# fitness_logger.net
KiCad netlist of a schematic drawn in EAGLE
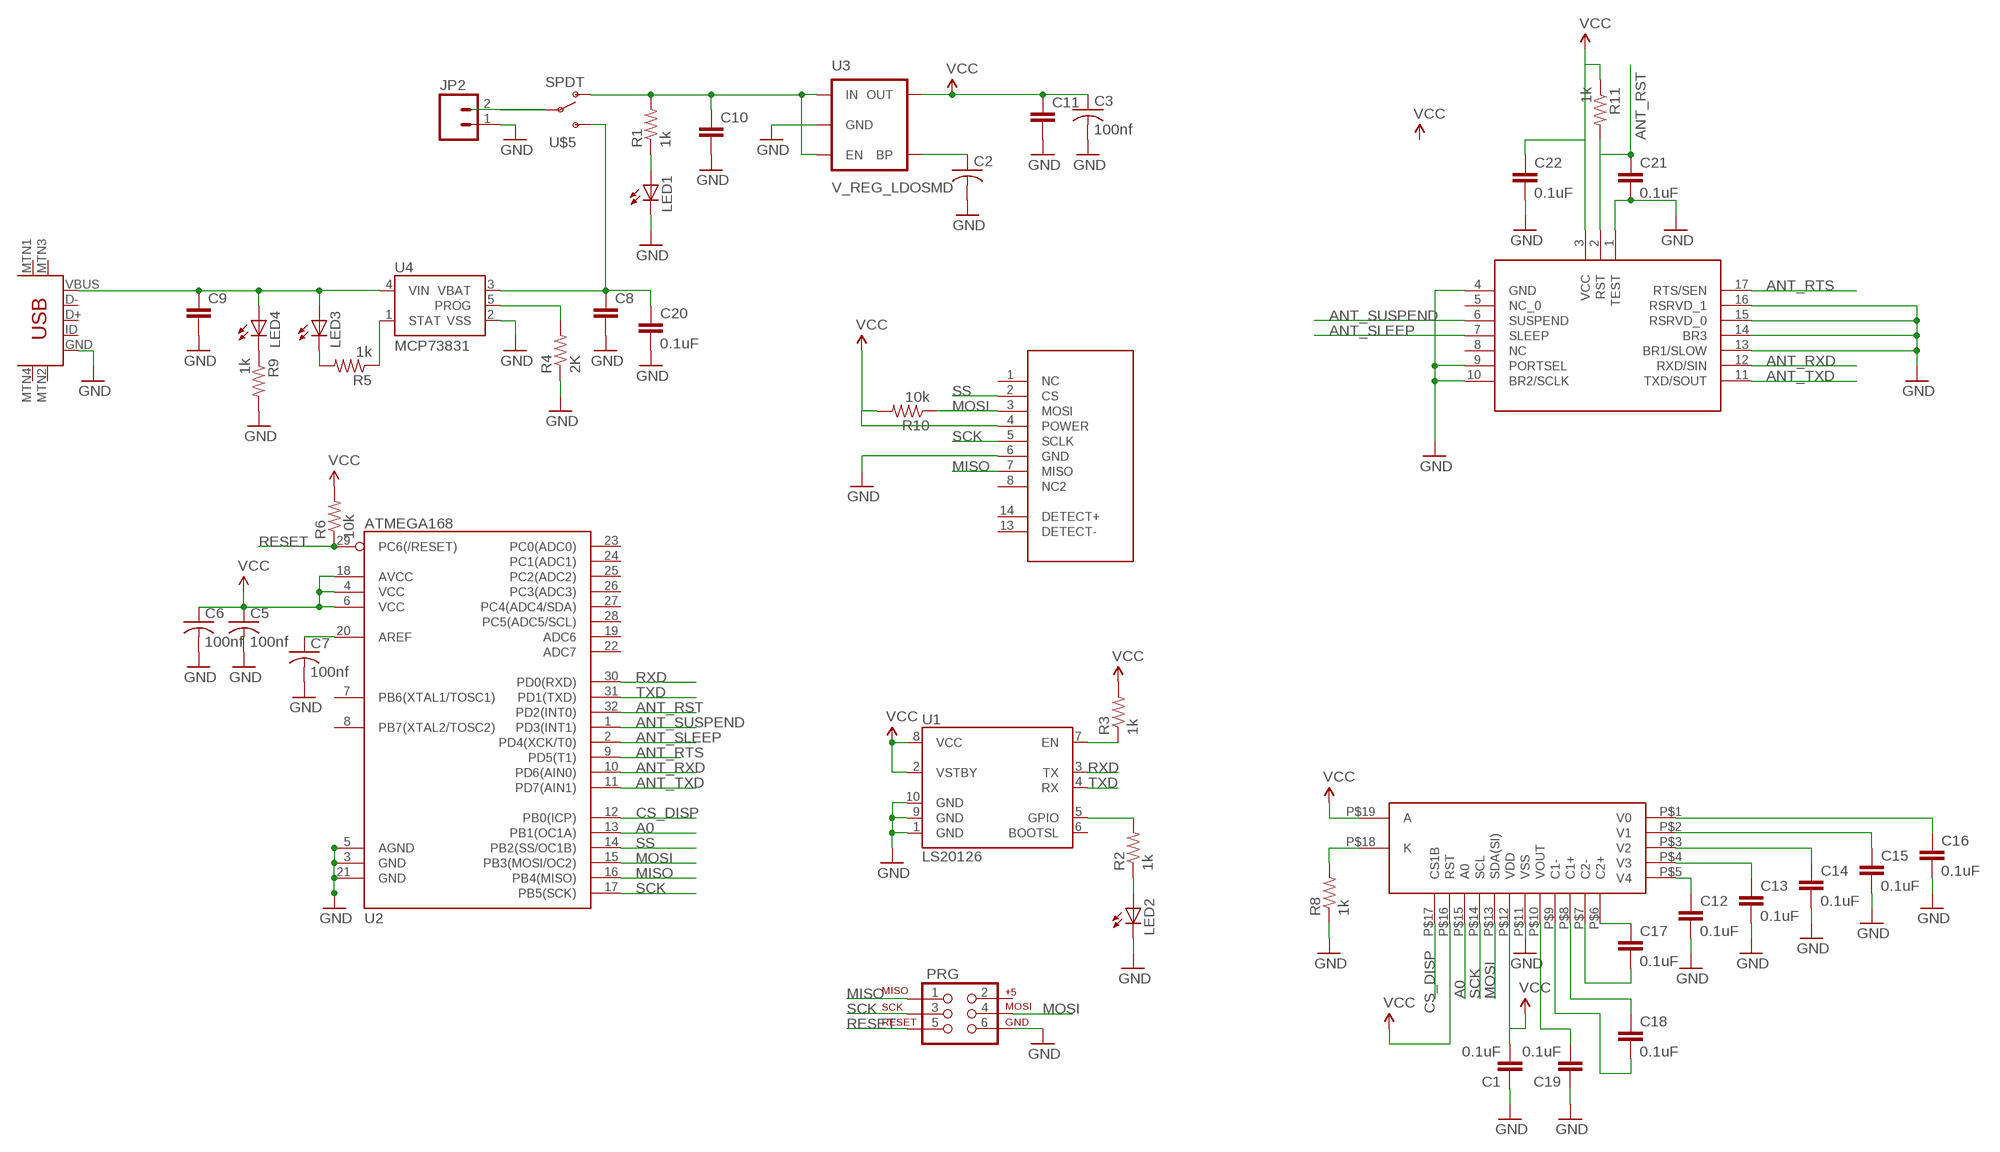
[diagram p0: schematic, sheet 1]

(export (version "E")
  (design (tool "Eeschema 10.0.6"))
  (components
    (comp (ref "C1")
      (value "0.1uF")
      (footprint "eagle-import:0402-CAP")
      (libsource (lib "eagle-import") (part "0.1UF-25V(+80/-20%)(0603)"))
    )
    (comp (ref "C2")
      (value "C-USC0603")
      (footprint "eagle-import:C0603")
      (libsource (lib "eagle-import") (part "C-USC0603"))
    )
    (comp (ref "C3")
      (value "100nf")
      (footprint "eagle-import:C0603")
      (libsource (lib "eagle-import") (part "C-USC0603"))
    )
    (comp (ref "C5")
      (value "100nf")
      (footprint "eagle-import:C0603")
      (libsource (lib "eagle-import") (part "C-USC0603"))
    )
    (comp (ref "C6")
      (value "100nf")
      (footprint "eagle-import:C0603")
      (libsource (lib "eagle-import") (part "C-USC0603"))
    )
    (comp (ref "C7")
      (value "100nf")
      (footprint "eagle-import:C0603")
      (libsource (lib "eagle-import") (part "C-USC0603"))
    )
    (comp (ref "C8")
      (value "CAP1210")
      (footprint "eagle-import:1210")
      (libsource (lib "eagle-import") (part "CAP1210"))
    )
    (comp (ref "C9")
      (value "CAP1210")
      (footprint "eagle-import:1210")
      (libsource (lib "eagle-import") (part "CAP1210"))
    )
    (comp (ref "C10")
      (value "CAP1210")
      (footprint "eagle-import:1210")
      (libsource (lib "eagle-import") (part "CAP1210"))
    )
    (comp (ref "C11")
      (value "CAP1210")
      (footprint "eagle-import:1210")
      (libsource (lib "eagle-import") (part "CAP1210"))
    )
    (comp (ref "C12")
      (value "0.1uF")
      (footprint "eagle-import:0402-CAP")
      (libsource (lib "eagle-import") (part "0.1UF-25V(+80/-20%)(0603)"))
    )
    (comp (ref "C13")
      (value "0.1uF")
      (footprint "eagle-import:0402-CAP")
      (libsource (lib "eagle-import") (part "0.1UF-25V(+80/-20%)(0603)"))
    )
    (comp (ref "C14")
      (value "0.1uF")
      (footprint "eagle-import:0402-CAP")
      (libsource (lib "eagle-import") (part "0.1UF-25V(+80/-20%)(0603)"))
    )
    (comp (ref "C15")
      (value "0.1uF")
      (footprint "eagle-import:0402-CAP")
      (libsource (lib "eagle-import") (part "0.1UF-25V(+80/-20%)(0603)"))
    )
    (comp (ref "C16")
      (value "0.1uF")
      (footprint "eagle-import:0402-CAP")
      (libsource (lib "eagle-import") (part "0.1UF-25V(+80/-20%)(0603)"))
    )
    (comp (ref "C17")
      (value "0.1uF")
      (footprint "eagle-import:0402-CAP")
      (libsource (lib "eagle-import") (part "0.1UF-25V(+80/-20%)(0603)"))
    )
    (comp (ref "C18")
      (value "0.1uF")
      (footprint "eagle-import:0402-CAP")
      (libsource (lib "eagle-import") (part "0.1UF-25V(+80/-20%)(0603)"))
    )
    (comp (ref "C19")
      (value "0.1uF")
      (footprint "eagle-import:0402-CAP")
      (libsource (lib "eagle-import") (part "0.1UF-25V(+80/-20%)(0603)"))
    )
    (comp (ref "C20")
      (value "0.1uF")
      (footprint "eagle-import:0402-CAP")
      (libsource (lib "eagle-import") (part "0.1UF-25V(+80/-20%)(0603)"))
    )
    (comp (ref "C21")
      (value "0.1uF")
      (footprint "eagle-import:0402-CAP")
      (libsource (lib "eagle-import") (part "0.1UF-25V(+80/-20%)(0603)"))
    )
    (comp (ref "C22")
      (value "0.1uF")
      (footprint "eagle-import:0402-CAP")
      (libsource (lib "eagle-import") (part "0.1UF-25V(+80/-20%)(0603)"))
    )
    (comp (ref "JP2")
      (value "M02PTH3")
      (footprint "eagle-import:1X02_LONGPADS")
      (libsource (lib "eagle-import") (part "M02PTH3"))
    )
    (comp (ref "LED1")
      (value "LEDCHIPLED_0603")
      (footprint "eagle-import:CHIPLED_0603")
      (libsource (lib "eagle-import") (part "LEDCHIPLED_0603"))
    )
    (comp (ref "LED2")
      (value "LEDCHIPLED_0603")
      (footprint "eagle-import:CHIPLED_0603")
      (libsource (lib "eagle-import") (part "LEDCHIPLED_0603"))
    )
    (comp (ref "LED3")
      (value "LEDCHIPLED_0603")
      (footprint "eagle-import:CHIPLED_0603")
      (libsource (lib "eagle-import") (part "LEDCHIPLED_0603"))
    )
    (comp (ref "LED4")
      (value "LEDCHIPLED_0603")
      (footprint "eagle-import:CHIPLED_0603")
      (libsource (lib "eagle-import") (part "LEDCHIPLED_0603"))
    )
    (comp (ref "PRG")
      (value "AVR_SPI_PRG_6PTH")
      (footprint "eagle-import:2X3")
      (libsource (lib "eagle-import") (part "AVR_SPI_PRG_6PTH"))
    )
    (comp (ref "R1")
      (value "1k")
      (footprint "eagle-import:0603-RES")
      (libsource (lib "eagle-import") (part "RESISTOR0603-RES"))
    )
    (comp (ref "R2")
      (value "1k")
      (footprint "eagle-import:0603-RES")
      (libsource (lib "eagle-import") (part "RESISTOR0603-RES"))
    )
    (comp (ref "R3")
      (value "1k")
      (footprint "eagle-import:0603-RES")
      (libsource (lib "eagle-import") (part "RESISTOR0603-RES"))
    )
    (comp (ref "R4")
      (value "2K")
      (footprint "eagle-import:0603-RES")
      (libsource (lib "eagle-import") (part "RESISTOR0603-RES"))
    )
    (comp (ref "R5")
      (value "1k")
      (footprint "eagle-import:0603-RES")
      (libsource (lib "eagle-import") (part "RESISTOR0603-RES"))
    )
    (comp (ref "R6")
      (value "10k")
      (footprint "eagle-import:0603-RES")
      (libsource (lib "eagle-import") (part "RESISTOR0603-RES"))
    )
    (comp (ref "R8")
      (value "1k")
      (footprint "eagle-import:0603-RES")
      (libsource (lib "eagle-import") (part "RESISTOR0603-RES"))
    )
    (comp (ref "R9")
      (value "1k")
      (footprint "eagle-import:0603-RES")
      (libsource (lib "eagle-import") (part "RESISTOR0603-RES"))
    )
    (comp (ref "R10")
      (value "10k")
      (footprint "eagle-import:0603-RES")
      (libsource (lib "eagle-import") (part "RESISTOR0603-RES"))
    )
    (comp (ref "R11")
      (value "1k")
      (footprint "eagle-import:0603-RES")
      (libsource (lib "eagle-import") (part "RESISTOR0603-RES"))
    )
    (comp (ref "U$1")
      (value "USB-MINIB-5PIN")
      (footprint "eagle-import:USB-MINIB")
      (libsource (lib "eagle-import") (part "USB-MINIB-5PIN"))
    )
    (comp (ref "U$2")
      (value "ANTAP281M4IB")
      (footprint "eagle-import:ANTAP281M4IB")
      (libsource (lib "eagle-import") (part "ANTAP281M4IB"))
    )
    (comp (ref "U$3")
      (value "NHD-C12832A1Z")
      (footprint "eagle-import:NHD-C12832A1Z")
      (libsource (lib "eagle-import") (part "NHD-C12832A1Z"))
    )
    (comp (ref "U$4")
      (value "MICRO_SD")
      (footprint "eagle-import:MICRO_SD_MOLEX")
      (libsource (lib "eagle-import") (part "MICRO_SD"))
    )
    (comp (ref "U$5")
      (value "SPDT")
      (footprint "eagle-import:SPDT-SMD")
      (libsource (lib "eagle-import") (part "SPDT"))
    )
    (comp (ref "U1")
      (value "LS20126")
      (footprint "eagle-import:LS20126")
      (libsource (lib "eagle-import") (part "LS20126"))
    )
    (comp (ref "U2")
      (value "ATMEGA168")
      (footprint "eagle-import:TQFP32-08")
      (libsource (lib "eagle-import") (part "ATMEGA168"))
    )
    (comp (ref "U3")
      (value "V_REG_LDOSMD")
      (footprint "eagle-import:SOT23-5")
      (libsource (lib "eagle-import") (part "V_REG_LDOSMD"))
    )
    (comp (ref "U4")
      (value "MCP73831")
      (footprint "eagle-import:SOT23-5")
      (libsource (lib "eagle-import") (part "MCP73831"))
    )
  )
  (nets
    (net (code "1") (name "/A0") (class "Default")
      (node (ref "U$3") (pin "P$15") (pinfunction "A0_P$15") (pintype "bidirectional"))
      (node (ref "U2") (pin "13") (pinfunction "PB1(OC1A)_13") (pintype "bidirectional"))
    )
    (net (code "2") (name "/ANT_RST") (class "Default")
      (node (ref "C21") (pin "1") (pinfunction "1_1") (pintype "passive"))
      (node (ref "R11") (pin "2") (pinfunction "2_2") (pintype "passive"))
      (node (ref "U$2") (pin "2") (pinfunction "RST_2") (pintype "bidirectional"))
      (node (ref "U2") (pin "32") (pinfunction "PD2(INT0)_32") (pintype "bidirectional"))
    )
    (net (code "3") (name "/ANT_RTS") (class "Default")
      (node (ref "U$2") (pin "17") (pinfunction "RTS/SEN_17") (pintype "bidirectional"))
      (node (ref "U2") (pin "9") (pinfunction "PD5(T1)_9") (pintype "bidirectional"))
    )
    (net (code "4") (name "/ANT_RXD") (class "Default")
      (node (ref "U$2") (pin "12") (pinfunction "RXD/SIN_12") (pintype "bidirectional"))
      (node (ref "U2") (pin "10") (pinfunction "PD6(AIN0)_10") (pintype "bidirectional"))
    )
    (net (code "5") (name "/ANT_SLEEP") (class "Default")
      (node (ref "U$2") (pin "7") (pinfunction "SLEEP_7") (pintype "bidirectional"))
      (node (ref "U2") (pin "2") (pinfunction "PD4(XCK/T0)_2") (pintype "bidirectional"))
    )
    (net (code "6") (name "/ANT_SUSPEND") (class "Default")
      (node (ref "U$2") (pin "6") (pinfunction "SUSPEND_6") (pintype "bidirectional"))
      (node (ref "U2") (pin "1") (pinfunction "PD3(INT1)_1") (pintype "bidirectional"))
    )
    (net (code "7") (name "/ANT_TXD") (class "Default")
      (node (ref "U$2") (pin "11") (pinfunction "TXD/SOUT_11") (pintype "bidirectional"))
      (node (ref "U2") (pin "11") (pinfunction "PD7(AIN1)_11") (pintype "bidirectional"))
    )
    (net (code "8") (name "/CS_DISP") (class "Default")
      (node (ref "U$3") (pin "P$17") (pinfunction "CS1B_P$17") (pintype "bidirectional"))
      (node (ref "U2") (pin "12") (pinfunction "PB0(ICP)_12") (pintype "bidirectional"))
    )
    (net (code "9") (name "/MISO") (class "Default")
      (node (ref "PRG") (pin "1") (pinfunction "1_1") (pintype "passive"))
      (node (ref "U$4") (pin "7") (pinfunction "MISO_7") (pintype "bidirectional"))
      (node (ref "U2") (pin "16") (pinfunction "PB4(MISO)_16") (pintype "bidirectional"))
    )
    (net (code "10") (name "/MOSI") (class "Default")
      (node (ref "PRG") (pin "4") (pinfunction "4_4") (pintype "passive"))
      (node (ref "R10") (pin "1") (pinfunction "1_1") (pintype "passive"))
      (node (ref "U$3") (pin "P$13") (pinfunction "SDA(SI)_P$13") (pintype "bidirectional"))
      (node (ref "U$4") (pin "3") (pinfunction "MOSI_3") (pintype "bidirectional"))
      (node (ref "U2") (pin "15") (pinfunction "PB3(MOSI/OC2)_15") (pintype "bidirectional"))
    )
    (net (code "11") (name "/RESET") (class "Default")
      (node (ref "PRG") (pin "5") (pinfunction "5_5") (pintype "passive"))
      (node (ref "R6") (pin "1") (pinfunction "1_1") (pintype "passive"))
      (node (ref "U2") (pin "29") (pinfunction "PC6(/RESET)_29") (pintype "bidirectional"))
    )
    (net (code "12") (name "/RXD") (class "Default")
      (node (ref "U1") (pin "3") (pinfunction "TX_3") (pintype "bidirectional"))
      (node (ref "U2") (pin "30") (pinfunction "PD0(RXD)_30") (pintype "bidirectional"))
    )
    (net (code "13") (name "/SCK") (class "Default")
      (node (ref "PRG") (pin "3") (pinfunction "3_3") (pintype "passive"))
      (node (ref "U$3") (pin "P$14") (pinfunction "SCL_P$14") (pintype "bidirectional"))
      (node (ref "U$4") (pin "5") (pinfunction "SCLK_5") (pintype "bidirectional"))
      (node (ref "U2") (pin "17") (pinfunction "PB5(SCK)_17") (pintype "bidirectional"))
    )
    (net (code "14") (name "/SS") (class "Default")
      (node (ref "U$4") (pin "2") (pinfunction "CS_2") (pintype "bidirectional"))
      (node (ref "U2") (pin "14") (pinfunction "PB2(SS/OC1B)_14") (pintype "bidirectional"))
    )
    (net (code "15") (name "/TXD") (class "Default")
      (node (ref "U1") (pin "4") (pinfunction "RX_4") (pintype "bidirectional"))
      (node (ref "U2") (pin "31") (pinfunction "PD1(TXD)_31") (pintype "bidirectional"))
    )
    (net (code "16") (name "GND") (class "Default")
      (node (ref "C1") (pin "1") (pinfunction "1_1") (pintype "passive"))
      (node (ref "C10") (pin "2") (pinfunction "2_2") (pintype "passive"))
      (node (ref "C11") (pin "2") (pinfunction "2_2") (pintype "passive"))
      (node (ref "C12") (pin "2") (pinfunction "2_2") (pintype "passive"))
      (node (ref "C13") (pin "2") (pinfunction "2_2") (pintype "passive"))
      (node (ref "C14") (pin "2") (pinfunction "2_2") (pintype "passive"))
      (node (ref "C15") (pin "2") (pinfunction "2_2") (pintype "passive"))
      (node (ref "C16") (pin "2") (pinfunction "2_2") (pintype "passive"))
      (node (ref "C19") (pin "1") (pinfunction "1_1") (pintype "passive"))
      (node (ref "C2") (pin "2") (pinfunction "2_2") (pintype "passive"))
      (node (ref "C20") (pin "2") (pinfunction "2_2") (pintype "passive"))
      (node (ref "C21") (pin "2") (pinfunction "2_2") (pintype "passive"))
      (node (ref "C22") (pin "2") (pinfunction "2_2") (pintype "passive"))
      (node (ref "C3") (pin "2") (pinfunction "2_2") (pintype "passive"))
      (node (ref "C5") (pin "2") (pinfunction "2_2") (pintype "passive"))
      (node (ref "C6") (pin "2") (pinfunction "2_2") (pintype "passive"))
      (node (ref "C7") (pin "2") (pinfunction "2_2") (pintype "passive"))
      (node (ref "C8") (pin "2") (pinfunction "2_2") (pintype "passive"))
      (node (ref "C9") (pin "2") (pinfunction "2_2") (pintype "passive"))
      (node (ref "JP2") (pin "1") (pinfunction "1_1") (pintype "passive"))
      (node (ref "LED1") (pin "C") (pinfunction "C_C") (pintype "passive"))
      (node (ref "LED2") (pin "C") (pinfunction "C_C") (pintype "passive"))
      (node (ref "PRG") (pin "6") (pinfunction "6_6") (pintype "passive"))
      (node (ref "R4") (pin "1") (pinfunction "1_1") (pintype "passive"))
      (node (ref "R8") (pin "1") (pinfunction "1_1") (pintype "passive"))
      (node (ref "R9") (pin "2") (pinfunction "2_2") (pintype "passive"))
      (node (ref "U$1") (pin "GND") (pinfunction "GND_GND") (pintype "bidirectional"))
      (node (ref "U$2") (pin "1") (pinfunction "TEST_1") (pintype "bidirectional"))
      (node (ref "U$2") (pin "10") (pinfunction "BR2/SCLK_10") (pintype "bidirectional"))
      (node (ref "U$2") (pin "13") (pinfunction "BR1/SLOW_13") (pintype "bidirectional"))
      (node (ref "U$2") (pin "14") (pinfunction "BR3_14") (pintype "bidirectional"))
      (node (ref "U$2") (pin "15") (pinfunction "RSRVD_0_15") (pintype "bidirectional"))
      (node (ref "U$2") (pin "16") (pinfunction "RSRVD_1_16") (pintype "bidirectional"))
      (node (ref "U$2") (pin "4") (pinfunction "GND_4") (pintype "bidirectional"))
      (node (ref "U$2") (pin "9") (pinfunction "PORTSEL_9") (pintype "bidirectional"))
      (node (ref "U$3") (pin "P$11") (pinfunction "VSS_P$11") (pintype "bidirectional"))
      (node (ref "U$4") (pin "6") (pinfunction "GND_6") (pintype "bidirectional"))
      (node (ref "U1") (pin "1") (pinfunction "GND_1") (pintype "bidirectional"))
      (node (ref "U1") (pin "10") (pinfunction "GND_10") (pintype "bidirectional"))
      (node (ref "U1") (pin "9") (pinfunction "GND_9") (pintype "bidirectional"))
      (node (ref "U2") (pin "21") (pinfunction "GND_21") (pintype "bidirectional"))
      (node (ref "U2") (pin "3") (pinfunction "GND_3") (pintype "bidirectional"))
      (node (ref "U2") (pin "5") (pinfunction "AGND_5") (pintype "bidirectional"))
      (node (ref "U3") (pin "2") (pinfunction "GND_2") (pintype "input"))
      (node (ref "U4") (pin "2") (pinfunction "VSS_2") (pintype "power_in"))
    )
    (net (code "17") (name "Net-(JP2-Pad2)") (class "Default")
      (node (ref "JP2") (pin "2") (pinfunction "2_2") (pintype "passive"))
      (node (ref "U$5") (pin "2") (pinfunction "P_2") (pintype "passive"))
      (node (ref "U$5") (pin "5") (pinfunction "P_5") (pintype "passive"))
    )
    (net (code "18") (name "Net-(LED1-PadA)") (class "Default")
      (node (ref "LED1") (pin "A") (pinfunction "A_A") (pintype "passive"))
      (node (ref "R1") (pin "1") (pinfunction "1_1") (pintype "passive"))
    )
    (net (code "19") (name "Net-(LED2-PadA)") (class "Default")
      (node (ref "LED2") (pin "A") (pinfunction "A_A") (pintype "passive"))
      (node (ref "R2") (pin "1") (pinfunction "1_1") (pintype "passive"))
    )
    (net (code "20") (name "Net-(LED3-PadC)") (class "Default")
      (node (ref "LED3") (pin "C") (pinfunction "C_C") (pintype "passive"))
      (node (ref "R5") (pin "2") (pinfunction "2_2") (pintype "passive"))
    )
    (net (code "21") (name "Net-(LED4-PadC)") (class "Default")
      (node (ref "LED4") (pin "C") (pinfunction "C_C") (pintype "passive"))
      (node (ref "R9") (pin "1") (pinfunction "1_1") (pintype "passive"))
    )
    (net (code "22") (name "Net-(U$3-C1+)") (class "Default")
      (node (ref "C18") (pin "1") (pinfunction "1_1") (pintype "passive"))
      (node (ref "U$3") (pin "P$8") (pinfunction "C1+_P$8") (pintype "bidirectional"))
    )
    (net (code "23") (name "Net-(U$3-C1-)") (class "Default")
      (node (ref "C18") (pin "2") (pinfunction "2_2") (pintype "passive"))
      (node (ref "U$3") (pin "P$9") (pinfunction "C1-_P$9") (pintype "bidirectional"))
    )
    (net (code "24") (name "Net-(U$3-C2+)") (class "Default")
      (node (ref "C17") (pin "1") (pinfunction "1_1") (pintype "passive"))
      (node (ref "U$3") (pin "P$6") (pinfunction "C2+_P$6") (pintype "bidirectional"))
    )
    (net (code "25") (name "Net-(U$3-C2-)") (class "Default")
      (node (ref "C17") (pin "2") (pinfunction "2_2") (pintype "passive"))
      (node (ref "U$3") (pin "P$7") (pinfunction "C2-_P$7") (pintype "bidirectional"))
    )
    (net (code "26") (name "Net-(U$3-K)") (class "Default")
      (node (ref "R8") (pin "2") (pinfunction "2_2") (pintype "passive"))
      (node (ref "U$3") (pin "P$18") (pinfunction "K_P$18") (pintype "bidirectional"))
    )
    (net (code "27") (name "Net-(U$3-V0)") (class "Default")
      (node (ref "C16") (pin "1") (pinfunction "1_1") (pintype "passive"))
      (node (ref "U$3") (pin "P$1") (pinfunction "V0_P$1") (pintype "bidirectional"))
    )
    (net (code "28") (name "Net-(U$3-V1)") (class "Default")
      (node (ref "C15") (pin "1") (pinfunction "1_1") (pintype "passive"))
      (node (ref "U$3") (pin "P$2") (pinfunction "V1_P$2") (pintype "bidirectional"))
    )
    (net (code "29") (name "Net-(U$3-V2)") (class "Default")
      (node (ref "C14") (pin "1") (pinfunction "1_1") (pintype "passive"))
      (node (ref "U$3") (pin "P$3") (pinfunction "V2_P$3") (pintype "bidirectional"))
    )
    (net (code "30") (name "Net-(U$3-V3)") (class "Default")
      (node (ref "C13") (pin "1") (pinfunction "1_1") (pintype "passive"))
      (node (ref "U$3") (pin "P$4") (pinfunction "V3_P$4") (pintype "bidirectional"))
    )
    (net (code "31") (name "Net-(U$3-V4)") (class "Default")
      (node (ref "C12") (pin "1") (pinfunction "1_1") (pintype "passive"))
      (node (ref "U$3") (pin "P$5") (pinfunction "V4_P$5") (pintype "bidirectional"))
    )
    (net (code "32") (name "Net-(U$3-VOUT)") (class "Default")
      (node (ref "C19") (pin "2") (pinfunction "2_2") (pintype "passive"))
      (node (ref "U$3") (pin "P$10") (pinfunction "VOUT_P$10") (pintype "bidirectional"))
    )
    (net (code "33") (name "Net-(U1-EN)") (class "Default")
      (node (ref "R3") (pin "1") (pinfunction "1_1") (pintype "passive"))
      (node (ref "U1") (pin "7") (pinfunction "EN_7") (pintype "bidirectional"))
    )
    (net (code "34") (name "Net-(U1-GPIO)") (class "Default")
      (node (ref "R2") (pin "2") (pinfunction "2_2") (pintype "passive"))
      (node (ref "U1") (pin "5") (pinfunction "GPIO_5") (pintype "bidirectional"))
    )
    (net (code "35") (name "Net-(U2-AREF)") (class "Default")
      (node (ref "C7") (pin "1") (pinfunction "1_1") (pintype "passive"))
      (node (ref "U2") (pin "20") (pinfunction "AREF_20") (pintype "bidirectional"))
    )
    (net (code "36") (name "Net-(U3-BP)") (class "Default")
      (node (ref "C2") (pin "1") (pinfunction "1_1") (pintype "passive"))
      (node (ref "U3") (pin "4") (pinfunction "BP_4") (pintype "input"))
    )
    (net (code "37") (name "Net-(U3-EN)") (class "Default")
      (node (ref "C10") (pin "1") (pinfunction "1_1") (pintype "passive"))
      (node (ref "R1") (pin "2") (pinfunction "2_2") (pintype "passive"))
      (node (ref "U$5") (pin "1") (pinfunction "O_1") (pintype "passive"))
      (node (ref "U$5") (pin "4") (pinfunction "O_4") (pintype "passive"))
      (node (ref "U3") (pin "1") (pinfunction "IN_1") (pintype "input"))
      (node (ref "U3") (pin "3") (pinfunction "EN_3") (pintype "input"))
    )
    (net (code "38") (name "Net-(U4-PROG)") (class "Default")
      (node (ref "R4") (pin "2") (pinfunction "2_2") (pintype "passive"))
      (node (ref "U4") (pin "5") (pinfunction "PROG_5") (pintype "input"))
    )
    (net (code "39") (name "Net-(U4-STAT)") (class "Default")
      (node (ref "R5") (pin "1") (pinfunction "1_1") (pintype "passive"))
      (node (ref "U4") (pin "1") (pinfunction "STAT_1") (pintype "output"))
    )
    (net (code "40") (name "Net-(U4-VBAT)") (class "Default")
      (node (ref "C20") (pin "1") (pinfunction "1_1") (pintype "passive"))
      (node (ref "C8") (pin "1") (pinfunction "1_1") (pintype "passive"))
      (node (ref "U$5") (pin "3") (pinfunction "S_3") (pintype "passive"))
      (node (ref "U$5") (pin "6") (pinfunction "S_6") (pintype "passive"))
      (node (ref "U4") (pin "3") (pinfunction "VBAT_3") (pintype "power_in"))
    )
    (net (code "41") (name "Net-(U4-VIN)") (class "Default")
      (node (ref "C9") (pin "1") (pinfunction "1_1") (pintype "passive"))
      (node (ref "LED3") (pin "A") (pinfunction "A_A") (pintype "passive"))
      (node (ref "LED4") (pin "A") (pinfunction "A_A") (pintype "passive"))
      (node (ref "U$1") (pin "VBUS") (pinfunction "VBUS_VBUS") (pintype "bidirectional"))
      (node (ref "U4") (pin "4") (pinfunction "VIN_4") (pintype "power_in"))
    )
    (net (code "42") (name "VCC") (class "Default")
      (node (ref "C1") (pin "2") (pinfunction "2_2") (pintype "passive"))
      (node (ref "C11") (pin "1") (pinfunction "1_1") (pintype "passive"))
      (node (ref "C22") (pin "1") (pinfunction "1_1") (pintype "passive"))
      (node (ref "C3") (pin "1") (pinfunction "1_1") (pintype "passive"))
      (node (ref "C5") (pin "1") (pinfunction "1_1") (pintype "passive"))
      (node (ref "C6") (pin "1") (pinfunction "1_1") (pintype "passive"))
      (node (ref "R10") (pin "2") (pinfunction "2_2") (pintype "passive"))
      (node (ref "R11") (pin "1") (pinfunction "1_1") (pintype "passive"))
      (node (ref "R3") (pin "2") (pinfunction "2_2") (pintype "passive"))
      (node (ref "R6") (pin "2") (pinfunction "2_2") (pintype "passive"))
      (node (ref "U$2") (pin "3") (pinfunction "VCC_3") (pintype "bidirectional"))
      (node (ref "U$3") (pin "P$12") (pinfunction "VDD_P$12") (pintype "bidirectional"))
      (node (ref "U$3") (pin "P$16") (pinfunction "RST_P$16") (pintype "bidirectional"))
      (node (ref "U$3") (pin "P$19") (pinfunction "A_P$19") (pintype "bidirectional"))
      (node (ref "U$4") (pin "4") (pinfunction "POWER_4") (pintype "bidirectional"))
      (node (ref "U1") (pin "2") (pinfunction "VSTBY_2") (pintype "bidirectional"))
      (node (ref "U1") (pin "8") (pinfunction "VCC_8") (pintype "bidirectional"))
      (node (ref "U2") (pin "18") (pinfunction "AVCC_18") (pintype "bidirectional"))
      (node (ref "U2") (pin "4") (pinfunction "VCC_4") (pintype "bidirectional"))
      (node (ref "U2") (pin "6") (pinfunction "VCC_6") (pintype "bidirectional"))
      (node (ref "U3") (pin "5") (pinfunction "OUT_5") (pintype "passive"))
    )
    (net (code "43") (name "unconnected-(PRG-Pad2)") (class "Default")
      (node (ref "PRG") (pin "2") (pinfunction "2_2") (pintype "passive"))
    )
    (net (code "44") (name "unconnected-(U$1-MTN1-PadMTN3)") (class "Default")
      (node (ref "U$1") (pin "MTN3") (pinfunction "MTN1_MTN3") (pintype "bidirectional"))
    )
    (net (code "45") (name "unconnected-(U$1-MTN2-PadMTN1)") (class "Default")
      (node (ref "U$1") (pin "MTN1") (pinfunction "MTN2_MTN1") (pintype "bidirectional"))
    )
    (net (code "46") (name "unconnected-(U$1-MTN3-PadMTN2)") (class "Default")
      (node (ref "U$1") (pin "MTN2") (pinfunction "MTN3_MTN2") (pintype "bidirectional"))
    )
    (net (code "47") (name "unconnected-(U$1-PadD+)") (class "Default")
      (node (ref "U$1") (pin "D+") (pinfunction "D+_D+") (pintype "bidirectional"))
    )
    (net (code "48") (name "unconnected-(U$1-PadD-)") (class "Default")
      (node (ref "U$1") (pin "D-") (pinfunction "D-_D-") (pintype "bidirectional"))
    )
    (net (code "49") (name "unconnected-(U$1-PadID)") (class "Default")
      (node (ref "U$1") (pin "ID") (pinfunction "ID_ID") (pintype "bidirectional"))
    )
    (net (code "50") (name "unconnected-(U$1-PadMTN4)") (class "Default")
      (node (ref "U$1") (pin "MTN4") (pinfunction "MTN4_MTN4") (pintype "bidirectional"))
    )
    (net (code "51") (name "unconnected-(U$2-NC-Pad8)") (class "Default")
      (node (ref "U$2") (pin "8") (pinfunction "NC_8") (pintype "bidirectional"))
    )
    (net (code "52") (name "unconnected-(U$2-NC_0-Pad5)") (class "Default")
      (node (ref "U$2") (pin "5") (pinfunction "NC_0_5") (pintype "bidirectional"))
    )
    (net (code "53") (name "unconnected-(U$4-DETECT+-Pad14)") (class "Default")
      (node (ref "U$4") (pin "14") (pinfunction "DETECT+_14") (pintype "bidirectional"))
    )
    (net (code "54") (name "unconnected-(U$4-DETECT--Pad13)") (class "Default")
      (node (ref "U$4") (pin "13") (pinfunction "DETECT-_13") (pintype "bidirectional"))
    )
    (net (code "55") (name "unconnected-(U$4-NC-Pad1)") (class "Default")
      (node (ref "U$4") (pin "1") (pinfunction "NC_1") (pintype "bidirectional"))
    )
    (net (code "56") (name "unconnected-(U$4-NC2-Pad8)") (class "Default")
      (node (ref "U$4") (pin "8") (pinfunction "NC2_8") (pintype "bidirectional"))
    )
    (net (code "57") (name "unconnected-(U1-BOOTSL-Pad6)") (class "Default")
      (node (ref "U1") (pin "6") (pinfunction "BOOTSL_6") (pintype "bidirectional"))
    )
    (net (code "58") (name "unconnected-(U2-ADC6-Pad19)") (class "Default")
      (node (ref "U2") (pin "19") (pinfunction "ADC6_19") (pintype "bidirectional"))
    )
    (net (code "59") (name "unconnected-(U2-ADC7-Pad22)") (class "Default")
      (node (ref "U2") (pin "22") (pinfunction "ADC7_22") (pintype "bidirectional"))
    )
    (net (code "60") (name "unconnected-(U2-PB6(XTAL1{slash}TOSC1)-Pad7)") (class "Default")
      (node (ref "U2") (pin "7") (pinfunction "PB6(XTAL1/TOSC1)_7") (pintype "bidirectional"))
    )
    (net (code "61") (name "unconnected-(U2-PB7(XTAL2{slash}TOSC2)-Pad8)") (class "Default")
      (node (ref "U2") (pin "8") (pinfunction "PB7(XTAL2/TOSC2)_8") (pintype "bidirectional"))
    )
    (net (code "62") (name "unconnected-(U2-PC0(ADC0)-Pad23)") (class "Default")
      (node (ref "U2") (pin "23") (pinfunction "PC0(ADC0)_23") (pintype "bidirectional"))
    )
    (net (code "63") (name "unconnected-(U2-PC1(ADC1)-Pad24)") (class "Default")
      (node (ref "U2") (pin "24") (pinfunction "PC1(ADC1)_24") (pintype "bidirectional"))
    )
    (net (code "64") (name "unconnected-(U2-PC2(ADC2)-Pad25)") (class "Default")
      (node (ref "U2") (pin "25") (pinfunction "PC2(ADC2)_25") (pintype "bidirectional"))
    )
    (net (code "65") (name "unconnected-(U2-PC3(ADC3)-Pad26)") (class "Default")
      (node (ref "U2") (pin "26") (pinfunction "PC3(ADC3)_26") (pintype "bidirectional"))
    )
    (net (code "66") (name "unconnected-(U2-PC4(ADC4{slash}SDA)-Pad27)") (class "Default")
      (node (ref "U2") (pin "27") (pinfunction "PC4(ADC4/SDA)_27") (pintype "bidirectional"))
    )
    (net (code "67") (name "unconnected-(U2-PC5(ADC5{slash}SCL)-Pad28)") (class "Default")
      (node (ref "U2") (pin "28") (pinfunction "PC5(ADC5/SCL)_28") (pintype "bidirectional"))
    )
  )
)
